# battery_tester.net
KiCad netlist of a schematic drawn in EAGLE
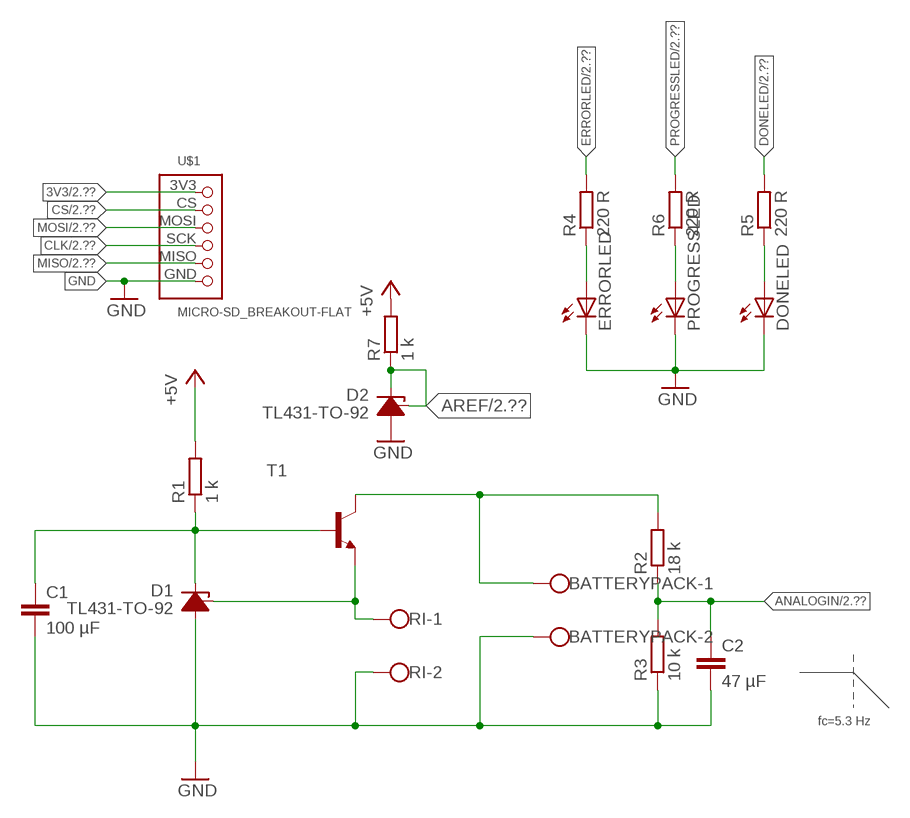
[diagram p0: schematic, sheet 1]
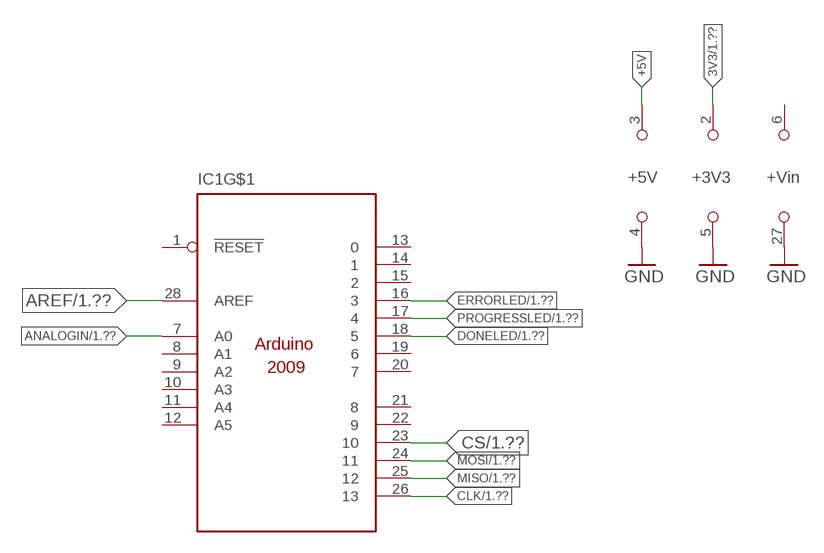
[diagram p1: schematic, sheet 2]

(export (version "E")
  (design (tool "Eeschema 10.0.6"))
  (components
    (comp (ref "BATTERYPACK")
      (value "W237-102")
      (footprint "eagle-import:W237-102")
      (fields (field (name "MPN") "237-102"))
      (libsource (lib "eagle-import") (part "W237-102"))
    )
    (comp (ref "C1")
      (value "100 µF")
      (footprint "eagle-import:C1206")
      (libsource (lib "eagle-import") (part "C-EUC1206"))
    )
    (comp (ref "C2")
      (value "47 µF")
      (footprint "eagle-import:C1206")
      (libsource (lib "eagle-import") (part "C-EUC1206"))
    )
    (comp (ref "D1")
      (value "TL431-TO-92")
      (footprint "eagle-import:TO-92")
      (libsource (lib "eagle-import") (part "TL431-TO-92"))
    )
    (comp (ref "D2")
      (value "TL431-TO-92")
      (footprint "eagle-import:TO-92")
      (libsource (lib "eagle-import") (part "TL431-TO-92"))
    )
    (comp (ref "DONELED")
      (value "LEDSML1206")
      (footprint "eagle-import:SML1206")
      (libsource (lib "eagle-import") (part "LEDSML1206"))
    )
    (comp (ref "ERRORLED")
      (value "LEDSML1206")
      (footprint "eagle-import:SML1206")
      (libsource (lib "eagle-import") (part "LEDSML1206"))
    )
    (comp (ref "PROGRESSLED")
      (value "LEDSML1206")
      (footprint "eagle-import:SML1206")
      (libsource (lib "eagle-import") (part "LEDSML1206"))
    )
    (comp (ref "R1")
      (value "1 k")
      (footprint "eagle-import:R1206")
      (libsource (lib "eagle-import") (part "R-EU_R1206"))
    )
    (comp (ref "R2")
      (value "18 k")
      (footprint "eagle-import:R1206")
      (libsource (lib "eagle-import") (part "R-EU_R1206"))
    )
    (comp (ref "R3")
      (value "10 k")
      (footprint "eagle-import:R1206")
      (libsource (lib "eagle-import") (part "R-EU_R1206"))
    )
    (comp (ref "R4")
      (value "220 R")
      (footprint "eagle-import:R1206")
      (libsource (lib "eagle-import") (part "R-EU_R1206"))
    )
    (comp (ref "R5")
      (value "220 R")
      (footprint "eagle-import:R1206")
      (libsource (lib "eagle-import") (part "R-EU_R1206"))
    )
    (comp (ref "R6")
      (value "220 R")
      (footprint "eagle-import:R1206")
      (libsource (lib "eagle-import") (part "R-EU_R1206"))
    )
    (comp (ref "R7")
      (value "1 k")
      (footprint "eagle-import:R1206")
      (libsource (lib "eagle-import") (part "R-EU_R1206"))
    )
    (comp (ref "RI")
      (value "W237-102")
      (footprint "eagle-import:W237-102")
      (fields (field (name "MPN") "237-102"))
      (libsource (lib "eagle-import") (part "W237-102"))
    )
    (comp (ref "T1")
      (value "-NPN-TO92")
      (footprint "eagle-import:TO92")
      (libsource (lib "eagle-import") (part "-NPN-TO92"))
    )
    (comp (ref "U$1")
      (value "MICRO-SD_BREAKOUT-FLAT")
      (footprint "eagle-import:MICRO-SD_BREAKOUT_FLAT")
      (libsource (lib "eagle-import") (part "MICRO-SD_BREAKOUT-FLAT"))
    )
    (comp (ref "IC1")
      (value "ARDUINO2009_22")
      (footprint "eagle-import:ARDUINO2009_2")
      (libsource (lib "eagle-import") (part "ARDUINO2009_22"))
    )
  )
  (nets
    (net (code "1") (name "+5V") (class "Default")
      (node (ref "IC1") (pin "3") (pinfunction "+5V_3") (pintype "power_in"))
      (node (ref "R1") (pin "2") (pinfunction "2_2") (pintype "passive"))
      (node (ref "R7") (pin "2") (pinfunction "2_2") (pintype "passive"))
    )
    (net (code "2") (name "+VIN") (class "Default")
      (node (ref "IC1") (pin "6") (pinfunction "+VIN_6") (pintype "power_in"))
    )
    (net (code "3") (name "3V3") (class "Default")
      (node (ref "IC1") (pin "2") (pinfunction "+3V3_2") (pintype "power_in"))
      (node (ref "U$1") (pin "3V3") (pinfunction "3V3_3V3") (pintype "bidirectional"))
    )
    (net (code "4") (name "ANALOGIN") (class "Default")
      (node (ref "C2") (pin "1") (pinfunction "1_1") (pintype "passive"))
      (node (ref "IC1") (pin "7") (pinfunction "A0_7") (pintype "bidirectional"))
      (node (ref "R2") (pin "1") (pinfunction "1_1") (pintype "passive"))
      (node (ref "R3") (pin "2") (pinfunction "2_2") (pintype "passive"))
    )
    (net (code "5") (name "AREF") (class "Default")
      (node (ref "D2") (pin "1") (pinfunction "J_1") (pintype "passive"))
      (node (ref "D2") (pin "3") (pinfunction "K_3") (pintype "passive"))
      (node (ref "IC1") (pin "28") (pinfunction "AREF_28") (pintype "bidirectional"))
      (node (ref "R7") (pin "1") (pinfunction "1_1") (pintype "passive"))
    )
    (net (code "6") (name "CLK") (class "Default")
      (node (ref "IC1") (pin "26") (pinfunction "13_26") (pintype "bidirectional"))
      (node (ref "U$1") (pin "SCK") (pinfunction "SCK_SCK") (pintype "bidirectional"))
    )
    (net (code "7") (name "CS") (class "Default")
      (node (ref "IC1") (pin "23") (pinfunction "10_23") (pintype "bidirectional"))
      (node (ref "U$1") (pin "CS") (pinfunction "CS_CS") (pintype "bidirectional"))
    )
    (net (code "8") (name "DONELED") (class "Default")
      (node (ref "IC1") (pin "18") (pinfunction "5_18") (pintype "bidirectional"))
      (node (ref "R5") (pin "2") (pinfunction "2_2") (pintype "passive"))
    )
    (net (code "9") (name "ERRORLED") (class "Default")
      (node (ref "IC1") (pin "16") (pinfunction "3_16") (pintype "bidirectional"))
      (node (ref "R4") (pin "2") (pinfunction "2_2") (pintype "passive"))
    )
    (net (code "10") (name "GND") (class "Default")
      (node (ref "BATTERYPACK") (pin "2") (pinfunction "KL_2") (pintype "passive"))
      (node (ref "C1") (pin "2") (pinfunction "2_2") (pintype "passive"))
      (node (ref "C2") (pin "2") (pinfunction "2_2") (pintype "passive"))
      (node (ref "D1") (pin "2") (pinfunction "A_2") (pintype "passive"))
      (node (ref "D2") (pin "2") (pinfunction "A_2") (pintype "passive"))
      (node (ref "DONELED") (pin "C") (pinfunction "C_C") (pintype "passive"))
      (node (ref "ERRORLED") (pin "C") (pinfunction "C_C") (pintype "passive"))
      (node (ref "IC1") (pin "27") (pinfunction "GND_27") (pintype "power_in"))
      (node (ref "IC1") (pin "4") (pinfunction "GND_4") (pintype "power_in"))
      (node (ref "IC1") (pin "5") (pinfunction "GND_5") (pintype "power_in"))
      (node (ref "PROGRESSLED") (pin "C") (pinfunction "C_C") (pintype "passive"))
      (node (ref "R3") (pin "1") (pinfunction "1_1") (pintype "passive"))
      (node (ref "RI") (pin "2") (pinfunction "KL_2") (pintype "passive"))
      (node (ref "U$1") (pin "GND") (pinfunction "GND_GND") (pintype "bidirectional"))
    )
    (net (code "11") (name "MISO") (class "Default")
      (node (ref "IC1") (pin "25") (pinfunction "12_25") (pintype "bidirectional"))
      (node (ref "U$1") (pin "MISO") (pinfunction "MISO_MISO") (pintype "bidirectional"))
    )
    (net (code "12") (name "MOSI") (class "Default")
      (node (ref "IC1") (pin "24") (pinfunction "11_24") (pintype "bidirectional"))
      (node (ref "U$1") (pin "MOSI") (pinfunction "MOSI_MOSI") (pintype "bidirectional"))
    )
    (net (code "13") (name "Net-(BATTERYPACKA-KL)") (class "Default")
      (node (ref "BATTERYPACK") (pin "1") (pinfunction "KL_1") (pintype "passive"))
      (node (ref "R2") (pin "2") (pinfunction "2_2") (pintype "passive"))
      (node (ref "T1") (pin "3") (pinfunction "C_3") (pintype "passive"))
    )
    (net (code "14") (name "Net-(D1-J)") (class "Default")
      (node (ref "D1") (pin "1") (pinfunction "J_1") (pintype "passive"))
      (node (ref "RI") (pin "1") (pinfunction "KL_1") (pintype "passive"))
      (node (ref "T1") (pin "1") (pinfunction "E_1") (pintype "passive"))
    )
    (net (code "15") (name "Net-(D1-K)") (class "Default")
      (node (ref "C1") (pin "1") (pinfunction "1_1") (pintype "passive"))
      (node (ref "D1") (pin "3") (pinfunction "K_3") (pintype "passive"))
      (node (ref "R1") (pin "1") (pinfunction "1_1") (pintype "passive"))
      (node (ref "T1") (pin "2") (pinfunction "B_2") (pintype "passive"))
    )
    (net (code "16") (name "Net-(DONELED-PadA)") (class "Default")
      (node (ref "DONELED") (pin "A") (pinfunction "A_A") (pintype "passive"))
      (node (ref "R5") (pin "1") (pinfunction "1_1") (pintype "passive"))
    )
    (net (code "17") (name "Net-(ERRORLED-PadA)") (class "Default")
      (node (ref "ERRORLED") (pin "A") (pinfunction "A_A") (pintype "passive"))
      (node (ref "R4") (pin "1") (pinfunction "1_1") (pintype "passive"))
    )
    (net (code "18") (name "Net-(PROGRESSLED-PadA)") (class "Default")
      (node (ref "PROGRESSLED") (pin "A") (pinfunction "A_A") (pintype "passive"))
      (node (ref "R6") (pin "1") (pinfunction "1_1") (pintype "passive"))
    )
    (net (code "19") (name "PROGRESSLED") (class "Default")
      (node (ref "IC1") (pin "17") (pinfunction "4_17") (pintype "bidirectional"))
      (node (ref "R6") (pin "2") (pinfunction "2_2") (pintype "passive"))
    )
    (net (code "20") (name "unconnected-(IC1A-0-Pad13)") (class "Default")
      (node (ref "IC1") (pin "13") (pinfunction "0_13") (pintype "bidirectional"))
    )
    (net (code "21") (name "unconnected-(IC1A-1-Pad14)") (class "Default")
      (node (ref "IC1") (pin "14") (pinfunction "1_14") (pintype "bidirectional"))
    )
    (net (code "22") (name "unconnected-(IC1A-2-Pad15)") (class "Default")
      (node (ref "IC1") (pin "15") (pinfunction "2_15") (pintype "bidirectional"))
    )
    (net (code "23") (name "unconnected-(IC1A-6-Pad19)") (class "Default")
      (node (ref "IC1") (pin "19") (pinfunction "6_19") (pintype "bidirectional"))
    )
    (net (code "24") (name "unconnected-(IC1A-7-Pad20)") (class "Default")
      (node (ref "IC1") (pin "20") (pinfunction "7_20") (pintype "bidirectional"))
    )
    (net (code "25") (name "unconnected-(IC1A-8-Pad21)") (class "Default")
      (node (ref "IC1") (pin "21") (pinfunction "8_21") (pintype "bidirectional"))
    )
    (net (code "26") (name "unconnected-(IC1A-9-Pad22)") (class "Default")
      (node (ref "IC1") (pin "22") (pinfunction "9_22") (pintype "bidirectional"))
    )
    (net (code "27") (name "unconnected-(IC1A-A1-Pad8)") (class "Default")
      (node (ref "IC1") (pin "8") (pinfunction "A1_8") (pintype "bidirectional"))
    )
    (net (code "28") (name "unconnected-(IC1A-A2-Pad9)") (class "Default")
      (node (ref "IC1") (pin "9") (pinfunction "A2_9") (pintype "bidirectional"))
    )
    (net (code "29") (name "unconnected-(IC1A-A3-Pad10)") (class "Default")
      (node (ref "IC1") (pin "10") (pinfunction "A3_10") (pintype "bidirectional"))
    )
    (net (code "30") (name "unconnected-(IC1A-A4-Pad11)") (class "Default")
      (node (ref "IC1") (pin "11") (pinfunction "A4_11") (pintype "bidirectional"))
    )
    (net (code "31") (name "unconnected-(IC1A-A5-Pad12)") (class "Default")
      (node (ref "IC1") (pin "12") (pinfunction "A5_12") (pintype "bidirectional"))
    )
    (net (code "32") (name "unconnected-(IC1A-~{RESET}-Pad1)") (class "Default")
      (node (ref "IC1") (pin "1") (pinfunction "~{RESET}_1") (pintype "bidirectional"))
    )
  )
)
